# Demux.net
KiCad netlist of a schematic drawn in Altium Designer
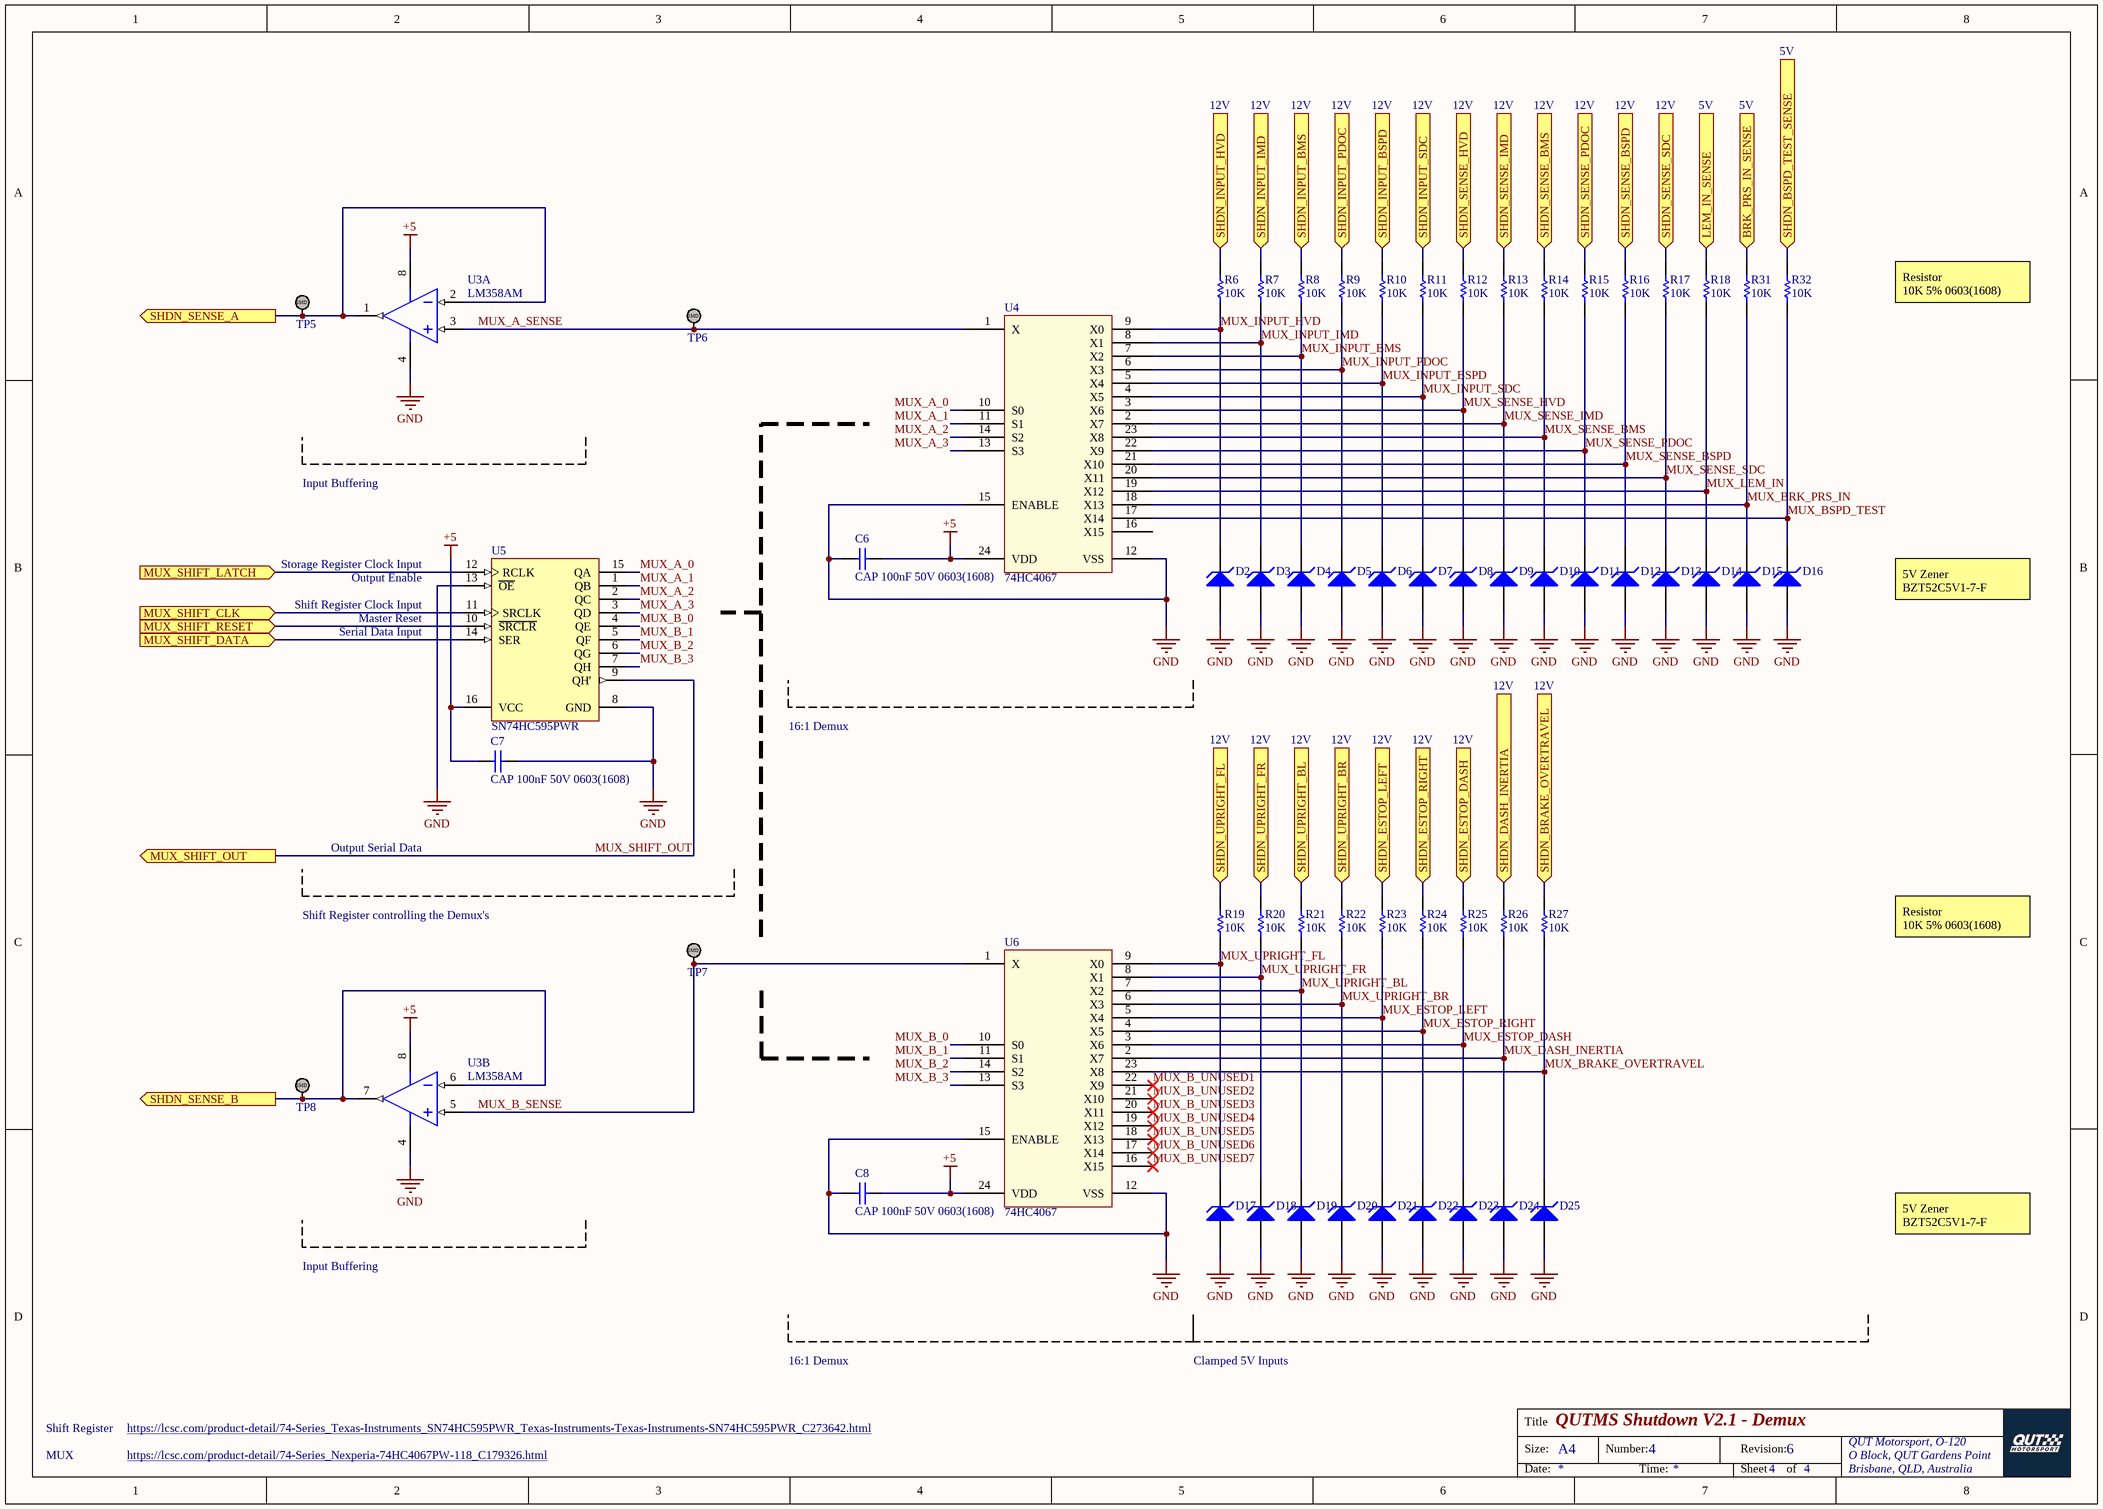
[diagram p0: Demux.SchDoc]

(export (version "E")
  (design (tool "Eeschema 10.0.6"))
  (components
    (comp (ref "C6")
      (value "CAP 100nF 50V 0603(1608)")
      (footprint "CAPC0603(1608)100_L")
      (description "CAP 100nF 50V ±5% 0603 (1608 Metric) Thickness 1mm SMD")
      (fields (field (name "TOLERANCE") "Â±5%"))
      (libsource (lib "Altium Content Vault") (part "CAP"))
    )
    (comp (ref "C7")
      (value "CAP 100nF 50V 0603(1608)")
      (footprint "CAPC0603(1608)100_L")
      (description "CAP 100nF 50V ±5% 0603 (1608 Metric) Thickness 1mm SMD")
      (fields (field (name "TOLERANCE") "Â±5%"))
      (libsource (lib "Altium Content Vault") (part "CAP"))
    )
    (comp (ref "C8")
      (value "CAP 100nF 50V 0603(1608)")
      (footprint "CAPC0603(1608)100_L")
      (description "CAP 100nF 50V ±5% 0603 (1608 Metric) Thickness 1mm SMD")
      (fields (field (name "TOLERANCE") "Â±5%"))
      (libsource (lib "Altium Content Vault") (part "CAP"))
    )
    (comp (ref "D2")
      (value "BZT52C5V1-7-F")
      (footprint "DIOD-SOD123_V")
      (description "Surface Mount Zener Diode, 5.1 V, -65 to 150 degC, 2-Pin SMD (SOD-123), RoHS, Tape and Reel")
      (fields (field (name "MANUFACTURER") "DiodesIncorporated"))
      (libsource (lib "Altium Content Vault") (part "DZEN-AK-2"))
    )
    (comp (ref "D3")
      (value "BZT52C5V1-7-F")
      (footprint "DIOD-SOD123_V")
      (description "Surface Mount Zener Diode, 5.1 V, -65 to 150 degC, 2-Pin SMD (SOD-123), RoHS, Tape and Reel")
      (fields (field (name "MANUFACTURER") "DiodesIncorporated"))
      (libsource (lib "Altium Content Vault") (part "DZEN-AK-2"))
    )
    (comp (ref "D4")
      (value "BZT52C5V1-7-F")
      (footprint "DIOD-SOD123_V")
      (description "Surface Mount Zener Diode, 5.1 V, -65 to 150 degC, 2-Pin SMD (SOD-123), RoHS, Tape and Reel")
      (fields (field (name "MANUFACTURER") "DiodesIncorporated"))
      (libsource (lib "Altium Content Vault") (part "DZEN-AK-2"))
    )
    (comp (ref "D5")
      (value "BZT52C5V1-7-F")
      (footprint "DIOD-SOD123_V")
      (description "Surface Mount Zener Diode, 5.1 V, -65 to 150 degC, 2-Pin SMD (SOD-123), RoHS, Tape and Reel")
      (fields (field (name "MANUFACTURER") "DiodesIncorporated"))
      (libsource (lib "Altium Content Vault") (part "DZEN-AK-2"))
    )
    (comp (ref "D6")
      (value "BZT52C5V1-7-F")
      (footprint "DIOD-SOD123_V")
      (description "Surface Mount Zener Diode, 5.1 V, -65 to 150 degC, 2-Pin SMD (SOD-123), RoHS, Tape and Reel")
      (fields (field (name "MANUFACTURER") "DiodesIncorporated"))
      (libsource (lib "Altium Content Vault") (part "DZEN-AK-2"))
    )
    (comp (ref "D7")
      (value "BZT52C5V1-7-F")
      (footprint "DIOD-SOD123_V")
      (description "Surface Mount Zener Diode, 5.1 V, -65 to 150 degC, 2-Pin SMD (SOD-123), RoHS, Tape and Reel")
      (fields (field (name "MANUFACTURER") "DiodesIncorporated"))
      (libsource (lib "Altium Content Vault") (part "DZEN-AK-2"))
    )
    (comp (ref "D8")
      (value "BZT52C5V1-7-F")
      (footprint "DIOD-SOD123_V")
      (description "Surface Mount Zener Diode, 5.1 V, -65 to 150 degC, 2-Pin SMD (SOD-123), RoHS, Tape and Reel")
      (fields (field (name "MANUFACTURER") "DiodesIncorporated"))
      (libsource (lib "Altium Content Vault") (part "DZEN-AK-2"))
    )
    (comp (ref "D9")
      (value "BZT52C5V1-7-F")
      (footprint "DIOD-SOD123_V")
      (description "Surface Mount Zener Diode, 5.1 V, -65 to 150 degC, 2-Pin SMD (SOD-123), RoHS, Tape and Reel")
      (fields (field (name "MANUFACTURER") "DiodesIncorporated"))
      (libsource (lib "Altium Content Vault") (part "DZEN-AK-2"))
    )
    (comp (ref "D10")
      (value "BZT52C5V1-7-F")
      (footprint "DIOD-SOD123_V")
      (description "Surface Mount Zener Diode, 5.1 V, -65 to 150 degC, 2-Pin SMD (SOD-123), RoHS, Tape and Reel")
      (fields (field (name "MANUFACTURER") "DiodesIncorporated"))
      (libsource (lib "Altium Content Vault") (part "DZEN-AK-2"))
    )
    (comp (ref "D11")
      (value "BZT52C5V1-7-F")
      (footprint "DIOD-SOD123_V")
      (description "Surface Mount Zener Diode, 5.1 V, -65 to 150 degC, 2-Pin SMD (SOD-123), RoHS, Tape and Reel")
      (fields (field (name "MANUFACTURER") "DiodesIncorporated"))
      (libsource (lib "Altium Content Vault") (part "DZEN-AK-2"))
    )
    (comp (ref "D12")
      (value "BZT52C5V1-7-F")
      (footprint "DIOD-SOD123_V")
      (description "Surface Mount Zener Diode, 5.1 V, -65 to 150 degC, 2-Pin SMD (SOD-123), RoHS, Tape and Reel")
      (fields (field (name "MANUFACTURER") "DiodesIncorporated"))
      (libsource (lib "Altium Content Vault") (part "DZEN-AK-2"))
    )
    (comp (ref "D13")
      (value "BZT52C5V1-7-F")
      (footprint "DIOD-SOD123_V")
      (description "Surface Mount Zener Diode, 5.1 V, -65 to 150 degC, 2-Pin SMD (SOD-123), RoHS, Tape and Reel")
      (fields (field (name "MANUFACTURER") "DiodesIncorporated"))
      (libsource (lib "Altium Content Vault") (part "DZEN-AK-2"))
    )
    (comp (ref "D14")
      (value "BZT52C5V1-7-F")
      (footprint "DIOD-SOD123_V")
      (description "Surface Mount Zener Diode, 5.1 V, -65 to 150 degC, 2-Pin SMD (SOD-123), RoHS, Tape and Reel")
      (fields (field (name "MANUFACTURER") "DiodesIncorporated"))
      (libsource (lib "Altium Content Vault") (part "DZEN-AK-2"))
    )
    (comp (ref "D15")
      (value "BZT52C5V1-7-F")
      (footprint "DIOD-SOD123_V")
      (description "Surface Mount Zener Diode, 5.1 V, -65 to 150 degC, 2-Pin SMD (SOD-123), RoHS, Tape and Reel")
      (fields (field (name "MANUFACTURER") "DiodesIncorporated"))
      (libsource (lib "Altium Content Vault") (part "DZEN-AK-2"))
    )
    (comp (ref "D16")
      (value "BZT52C5V1-7-F")
      (footprint "DIOD-SOD123_V")
      (description "Surface Mount Zener Diode, 5.1 V, -65 to 150 degC, 2-Pin SMD (SOD-123), RoHS, Tape and Reel")
      (fields (field (name "MANUFACTURER") "DiodesIncorporated"))
      (libsource (lib "Altium Content Vault") (part "DZEN-AK-2"))
    )
    (comp (ref "D17")
      (value "BZT52C5V1-7-F")
      (footprint "DIOD-SOD123_V")
      (description "Surface Mount Zener Diode, 5.1 V, -65 to 150 degC, 2-Pin SMD (SOD-123), RoHS, Tape and Reel")
      (fields (field (name "MANUFACTURER") "DiodesIncorporated"))
      (libsource (lib "Altium Content Vault") (part "DZEN-AK-2"))
    )
    (comp (ref "D18")
      (value "BZT52C5V1-7-F")
      (footprint "DIOD-SOD123_V")
      (description "Surface Mount Zener Diode, 5.1 V, -65 to 150 degC, 2-Pin SMD (SOD-123), RoHS, Tape and Reel")
      (fields (field (name "MANUFACTURER") "DiodesIncorporated"))
      (libsource (lib "Altium Content Vault") (part "DZEN-AK-2"))
    )
    (comp (ref "D19")
      (value "BZT52C5V1-7-F")
      (footprint "DIOD-SOD123_V")
      (description "Surface Mount Zener Diode, 5.1 V, -65 to 150 degC, 2-Pin SMD (SOD-123), RoHS, Tape and Reel")
      (fields (field (name "MANUFACTURER") "DiodesIncorporated"))
      (libsource (lib "Altium Content Vault") (part "DZEN-AK-2"))
    )
    (comp (ref "D20")
      (value "BZT52C5V1-7-F")
      (footprint "DIOD-SOD123_V")
      (description "Surface Mount Zener Diode, 5.1 V, -65 to 150 degC, 2-Pin SMD (SOD-123), RoHS, Tape and Reel")
      (fields (field (name "MANUFACTURER") "DiodesIncorporated"))
      (libsource (lib "Altium Content Vault") (part "DZEN-AK-2"))
    )
    (comp (ref "D21")
      (value "BZT52C5V1-7-F")
      (footprint "DIOD-SOD123_V")
      (description "Surface Mount Zener Diode, 5.1 V, -65 to 150 degC, 2-Pin SMD (SOD-123), RoHS, Tape and Reel")
      (fields (field (name "MANUFACTURER") "DiodesIncorporated"))
      (libsource (lib "Altium Content Vault") (part "DZEN-AK-2"))
    )
    (comp (ref "D22")
      (value "BZT52C5V1-7-F")
      (footprint "DIOD-SOD123_V")
      (description "Surface Mount Zener Diode, 5.1 V, -65 to 150 degC, 2-Pin SMD (SOD-123), RoHS, Tape and Reel")
      (fields (field (name "MANUFACTURER") "DiodesIncorporated"))
      (libsource (lib "Altium Content Vault") (part "DZEN-AK-2"))
    )
    (comp (ref "D23")
      (value "BZT52C5V1-7-F")
      (footprint "DIOD-SOD123_V")
      (description "Surface Mount Zener Diode, 5.1 V, -65 to 150 degC, 2-Pin SMD (SOD-123), RoHS, Tape and Reel")
      (fields (field (name "MANUFACTURER") "DiodesIncorporated"))
      (libsource (lib "Altium Content Vault") (part "DZEN-AK-2"))
    )
    (comp (ref "D24")
      (value "BZT52C5V1-7-F")
      (footprint "DIOD-SOD123_V")
      (description "Surface Mount Zener Diode, 5.1 V, -65 to 150 degC, 2-Pin SMD (SOD-123), RoHS, Tape and Reel")
      (fields (field (name "MANUFACTURER") "DiodesIncorporated"))
      (libsource (lib "Altium Content Vault") (part "DZEN-AK-2"))
    )
    (comp (ref "D25")
      (value "BZT52C5V1-7-F")
      (footprint "DIOD-SOD123_V")
      (description "Surface Mount Zener Diode, 5.1 V, -65 to 150 degC, 2-Pin SMD (SOD-123), RoHS, Tape and Reel")
      (fields (field (name "MANUFACTURER") "DiodesIncorporated"))
      (libsource (lib "Altium Content Vault") (part "DZEN-AK-2"))
    )
    (comp (ref "R6")
      (value "10K")
      (footprint "RESC0603(1608)_N")
      (description "10K 0.1W 5% 0603 (1608 Metric)  SMD")
      (fields (field (name "TOLERANCE") "5 %") (field (name "POWER") "0.1 W"))
      (libsource (lib "Altium Content Vault") (part "RES"))
    )
    (comp (ref "R7")
      (value "10K")
      (footprint "RESC0603(1608)_N")
      (description "10K 0.1W 5% 0603 (1608 Metric)  SMD")
      (fields (field (name "TOLERANCE") "5 %") (field (name "POWER") "0.1 W"))
      (libsource (lib "Altium Content Vault") (part "RES"))
    )
    (comp (ref "R8")
      (value "10K")
      (footprint "RESC0603(1608)_N")
      (description "10K 0.1W 5% 0603 (1608 Metric)  SMD")
      (fields (field (name "TOLERANCE") "5 %") (field (name "POWER") "0.1 W"))
      (libsource (lib "Altium Content Vault") (part "RES"))
    )
    (comp (ref "R9")
      (value "10K")
      (footprint "RESC0603(1608)_N")
      (description "10K 0.1W 5% 0603 (1608 Metric)  SMD")
      (fields (field (name "TOLERANCE") "5 %") (field (name "POWER") "0.1 W"))
      (libsource (lib "Altium Content Vault") (part "RES"))
    )
    (comp (ref "R10")
      (value "10K")
      (footprint "RESC0603(1608)_N")
      (description "10K 0.1W 5% 0603 (1608 Metric)  SMD")
      (fields (field (name "TOLERANCE") "5 %") (field (name "POWER") "0.1 W"))
      (libsource (lib "Altium Content Vault") (part "RES"))
    )
    (comp (ref "R11")
      (value "10K")
      (footprint "RESC0603(1608)_N")
      (description "10K 0.1W 5% 0603 (1608 Metric)  SMD")
      (fields (field (name "TOLERANCE") "5 %") (field (name "POWER") "0.1 W"))
      (libsource (lib "Altium Content Vault") (part "RES"))
    )
    (comp (ref "R12")
      (value "10K")
      (footprint "RESC0603(1608)_N")
      (description "10K 0.1W 5% 0603 (1608 Metric)  SMD")
      (fields (field (name "TOLERANCE") "5 %") (field (name "POWER") "0.1 W"))
      (libsource (lib "Altium Content Vault") (part "RES"))
    )
    (comp (ref "R13")
      (value "10K")
      (footprint "RESC0603(1608)_N")
      (description "10K 0.1W 5% 0603 (1608 Metric)  SMD")
      (fields (field (name "TOLERANCE") "5 %") (field (name "POWER") "0.1 W"))
      (libsource (lib "Altium Content Vault") (part "RES"))
    )
    (comp (ref "R14")
      (value "10K")
      (footprint "RESC0603(1608)_N")
      (description "10K 0.1W 5% 0603 (1608 Metric)  SMD")
      (fields (field (name "TOLERANCE") "5 %") (field (name "POWER") "0.1 W"))
      (libsource (lib "Altium Content Vault") (part "RES"))
    )
    (comp (ref "R15")
      (value "10K")
      (footprint "RESC0603(1608)_N")
      (description "10K 0.1W 5% 0603 (1608 Metric)  SMD")
      (fields (field (name "TOLERANCE") "5 %") (field (name "POWER") "0.1 W"))
      (libsource (lib "Altium Content Vault") (part "RES"))
    )
    (comp (ref "R16")
      (value "10K")
      (footprint "RESC0603(1608)_N")
      (description "10K 0.1W 5% 0603 (1608 Metric)  SMD")
      (fields (field (name "TOLERANCE") "5 %") (field (name "POWER") "0.1 W"))
      (libsource (lib "Altium Content Vault") (part "RES"))
    )
    (comp (ref "R17")
      (value "10K")
      (footprint "RESC0603(1608)_N")
      (description "10K 0.1W 5% 0603 (1608 Metric)  SMD")
      (fields (field (name "TOLERANCE") "5 %") (field (name "POWER") "0.1 W"))
      (libsource (lib "Altium Content Vault") (part "RES"))
    )
    (comp (ref "R18")
      (value "10K")
      (footprint "RESC0603(1608)_N")
      (description "10K 0.1W 5% 0603 (1608 Metric)  SMD")
      (fields (field (name "TOLERANCE") "5 %") (field (name "POWER") "0.1 W"))
      (libsource (lib "Altium Content Vault") (part "RES"))
    )
    (comp (ref "R19")
      (value "10K")
      (footprint "RESC0603(1608)_N")
      (description "10K 0.1W 5% 0603 (1608 Metric)  SMD")
      (fields (field (name "TOLERANCE") "5 %") (field (name "POWER") "0.1 W"))
      (libsource (lib "Altium Content Vault") (part "RES"))
    )
    (comp (ref "R20")
      (value "10K")
      (footprint "RESC0603(1608)_N")
      (description "10K 0.1W 5% 0603 (1608 Metric)  SMD")
      (fields (field (name "TOLERANCE") "5 %") (field (name "POWER") "0.1 W"))
      (libsource (lib "Altium Content Vault") (part "RES"))
    )
    (comp (ref "R21")
      (value "10K")
      (footprint "RESC0603(1608)_N")
      (description "10K 0.1W 5% 0603 (1608 Metric)  SMD")
      (fields (field (name "TOLERANCE") "5 %") (field (name "POWER") "0.1 W"))
      (libsource (lib "Altium Content Vault") (part "RES"))
    )
    (comp (ref "R22")
      (value "10K")
      (footprint "RESC0603(1608)_N")
      (description "10K 0.1W 5% 0603 (1608 Metric)  SMD")
      (fields (field (name "TOLERANCE") "5 %") (field (name "POWER") "0.1 W"))
      (libsource (lib "Altium Content Vault") (part "RES"))
    )
    (comp (ref "R23")
      (value "10K")
      (footprint "RESC0603(1608)_N")
      (description "10K 0.1W 5% 0603 (1608 Metric)  SMD")
      (fields (field (name "TOLERANCE") "5 %") (field (name "POWER") "0.1 W"))
      (libsource (lib "Altium Content Vault") (part "RES"))
    )
    (comp (ref "R24")
      (value "10K")
      (footprint "RESC0603(1608)_N")
      (description "10K 0.1W 5% 0603 (1608 Metric)  SMD")
      (fields (field (name "TOLERANCE") "5 %") (field (name "POWER") "0.1 W"))
      (libsource (lib "Altium Content Vault") (part "RES"))
    )
    (comp (ref "R25")
      (value "10K")
      (footprint "RESC0603(1608)_N")
      (description "10K 0.1W 5% 0603 (1608 Metric)  SMD")
      (fields (field (name "TOLERANCE") "5 %") (field (name "POWER") "0.1 W"))
      (libsource (lib "Altium Content Vault") (part "RES"))
    )
    (comp (ref "R26")
      (value "10K")
      (footprint "RESC0603(1608)_N")
      (description "10K 0.1W 5% 0603 (1608 Metric)  SMD")
      (fields (field (name "TOLERANCE") "5 %") (field (name "POWER") "0.1 W"))
      (libsource (lib "Altium Content Vault") (part "RES"))
    )
    (comp (ref "R27")
      (value "10K")
      (footprint "RESC0603(1608)_N")
      (description "10K 0.1W 5% 0603 (1608 Metric)  SMD")
      (fields (field (name "TOLERANCE") "5 %") (field (name "POWER") "0.1 W"))
      (libsource (lib "Altium Content Vault") (part "RES"))
    )
    (comp (ref "R31")
      (value "10K")
      (footprint "RESC0603(1608)_N")
      (description "10K 0.1W 5% 0603 (1608 Metric)  SMD")
      (fields (field (name "TOLERANCE") "5 %") (field (name "POWER") "0.1 W"))
      (libsource (lib "Altium Content Vault") (part "RES"))
    )
    (comp (ref "R32")
      (value "10K")
      (footprint "RESC0603(1608)_N")
      (description "10K 0.1W 5% 0603 (1608 Metric)  SMD")
      (fields (field (name "TOLERANCE") "5 %") (field (name "POWER") "0.1 W"))
      (libsource (lib "Altium Content Vault") (part "RES"))
    )
    (comp (ref "TP5")
      (value "TestPoint_SMD")
      (footprint "TestPointSMD")
      (libsource (lib "StandardTest") (part "TestPoint_SMD"))
    )
    (comp (ref "TP6")
      (value "TestPoint_SMD")
      (footprint "TestPointSMD")
      (libsource (lib "StandardTest") (part "TestPoint_SMD"))
    )
    (comp (ref "TP7")
      (value "TestPoint_SMD")
      (footprint "TestPointSMD")
      (libsource (lib "StandardTest") (part "TestPoint_SMD"))
    )
    (comp (ref "TP8")
      (value "TestPoint_SMD")
      (footprint "TestPointSMD")
      (libsource (lib "StandardTest") (part "TestPoint_SMD"))
    )
    (comp (ref "U3")
      (value "LM358AM")
      (footprint "D0008A_M")
      (description "Low Power Dual Operational Amplifier, 8-pin Narrow SOIC")
      (fields (field (name "MANUFACTURER") "Texas Instruments"))
      (libsource (lib "Altium Content Vault") (part "AMP-OPA-LM158-8"))
    )
    (comp (ref "U4")
      (value "74HC4067")
      (footprint "74HC4067 TSSOP24")
      (libsource (lib "QUTMS_MUXLibrary") (part "74HC4067"))
    )
    (comp (ref "U5")
      (value "SN74HC595PWR")
      (footprint "PW0016A_L")
      (description "8-Bit Shift Registers With 3-State Output Registers, PW0016A, LARGE T&R")
      (fields
        (field (name "GENERIC PART NUMBER") "SN74HC595")
        (field (name "MANUFACTURER") "Texas Instruments")
      )
      (libsource (lib "Altium Content Vault") (part "TI-SN74XHCT595X_SN74LV595A-16"))
    )
    (comp (ref "U6")
      (value "74HC4067")
      (footprint "74HC4067 TSSOP24")
      (libsource (lib "QUTMS_MUXLibrary") (part "74HC4067"))
    )
  )
  (nets
    (net (code "1") (name "+5") (class "Default")
      (node (ref "C6") (pin "1") (pinfunction "1_1") (pintype "passive"))
      (node (ref "C7") (pin "2") (pinfunction "2_2") (pintype "passive"))
      (node (ref "C8") (pin "1") (pinfunction "1_1") (pintype "passive"))
      (node (ref "U3") (pin "8") (pinfunction "V+_8") (pintype "power_in"))
      (node (ref "U4") (pin "24") (pinfunction "VDD_24") (pintype "passive"))
      (node (ref "U5") (pin "16") (pinfunction "VCC_16") (pintype "power_in"))
      (node (ref "U6") (pin "24") (pinfunction "VDD_24") (pintype "passive"))
    )
    (net (code "2") (name "/BRK_PRS_IN_SENSE") (class "Default")
      (node (ref "R31") (pin "1") (pinfunction "1_1") (pintype "passive"))
    )
    (net (code "3") (name "/LEM_IN_SENSE") (class "Default")
      (node (ref "R18") (pin "1") (pinfunction "1_1") (pintype "passive"))
    )
    (net (code "4") (name "/MUX_A_0") (class "Default")
      (node (ref "U4") (pin "10") (pinfunction "S0_10") (pintype "passive"))
      (node (ref "U5") (pin "15") (pinfunction "QA_15") (pintype "tri_state"))
    )
    (net (code "5") (name "/MUX_A_1") (class "Default")
      (node (ref "U4") (pin "11") (pinfunction "S1_11") (pintype "passive"))
      (node (ref "U5") (pin "1") (pinfunction "QB_1") (pintype "tri_state"))
    )
    (net (code "6") (name "/MUX_A_2") (class "Default")
      (node (ref "U4") (pin "14") (pinfunction "S2_14") (pintype "passive"))
      (node (ref "U5") (pin "2") (pinfunction "QC_2") (pintype "tri_state"))
    )
    (net (code "7") (name "/MUX_A_3") (class "Default")
      (node (ref "U4") (pin "13") (pinfunction "S3_13") (pintype "passive"))
      (node (ref "U5") (pin "3") (pinfunction "QD_3") (pintype "tri_state"))
    )
    (net (code "8") (name "/MUX_A_SENSE") (class "Default")
      (node (ref "TP6") (pin "1") (pinfunction "1_1") (pintype "passive"))
      (node (ref "U3") (pin "3") (pinfunction "INA+_3") (pintype "input"))
      (node (ref "U4") (pin "1") (pinfunction "X_1") (pintype "passive"))
    )
    (net (code "9") (name "/MUX_BRAKE_OVERTRAVEL") (class "Default")
      (node (ref "D25") (pin "2") (pinfunction "K_2") (pintype "passive"))
      (node (ref "R27") (pin "2") (pinfunction "2_2") (pintype "passive"))
      (node (ref "U6") (pin "23") (pinfunction "X8_23") (pintype "passive"))
    )
    (net (code "10") (name "/MUX_BRK_PRS_IN") (class "Default")
      (node (ref "D15") (pin "2") (pinfunction "K_2") (pintype "passive"))
      (node (ref "R31") (pin "2") (pinfunction "2_2") (pintype "passive"))
      (node (ref "U4") (pin "18") (pinfunction "X13_18") (pintype "passive"))
    )
    (net (code "11") (name "/MUX_BSPD_TEST") (class "Default")
      (node (ref "D16") (pin "2") (pinfunction "K_2") (pintype "passive"))
      (node (ref "R32") (pin "2") (pinfunction "2_2") (pintype "passive"))
      (node (ref "U4") (pin "17") (pinfunction "X14_17") (pintype "passive"))
    )
    (net (code "12") (name "/MUX_B_0") (class "Default")
      (node (ref "U5") (pin "4") (pinfunction "QE_4") (pintype "tri_state"))
      (node (ref "U6") (pin "10") (pinfunction "S0_10") (pintype "passive"))
    )
    (net (code "13") (name "/MUX_B_1") (class "Default")
      (node (ref "U5") (pin "5") (pinfunction "QF_5") (pintype "tri_state"))
      (node (ref "U6") (pin "11") (pinfunction "S1_11") (pintype "passive"))
    )
    (net (code "14") (name "/MUX_B_2") (class "Default")
      (node (ref "U5") (pin "6") (pinfunction "QG_6") (pintype "tri_state"))
      (node (ref "U6") (pin "14") (pinfunction "S2_14") (pintype "passive"))
    )
    (net (code "15") (name "/MUX_B_3") (class "Default")
      (node (ref "U5") (pin "7") (pinfunction "QH_7") (pintype "tri_state"))
      (node (ref "U6") (pin "13") (pinfunction "S3_13") (pintype "passive"))
    )
    (net (code "16") (name "/MUX_B_SENSE") (class "Default")
      (node (ref "TP7") (pin "1") (pinfunction "1_1") (pintype "passive"))
      (node (ref "U3") (pin "5") (pinfunction "INB+_5") (pintype "input"))
      (node (ref "U6") (pin "1") (pinfunction "X_1") (pintype "passive"))
    )
    (net (code "17") (name "/MUX_B_UNUSED1") (class "Default")
      (node (ref "U6") (pin "22") (pinfunction "X9_22") (pintype "passive+no_connect"))
    )
    (net (code "18") (name "/MUX_B_UNUSED2") (class "Default")
      (node (ref "U6") (pin "21") (pinfunction "X10_21") (pintype "passive+no_connect"))
    )
    (net (code "19") (name "/MUX_B_UNUSED3") (class "Default")
      (node (ref "U6") (pin "20") (pinfunction "X11_20") (pintype "passive+no_connect"))
    )
    (net (code "20") (name "/MUX_B_UNUSED4") (class "Default")
      (node (ref "U6") (pin "19") (pinfunction "X12_19") (pintype "passive+no_connect"))
    )
    (net (code "21") (name "/MUX_B_UNUSED5") (class "Default")
      (node (ref "U6") (pin "18") (pinfunction "X13_18") (pintype "passive+no_connect"))
    )
    (net (code "22") (name "/MUX_B_UNUSED6") (class "Default")
      (node (ref "U6") (pin "17") (pinfunction "X14_17") (pintype "passive+no_connect"))
    )
    (net (code "23") (name "/MUX_B_UNUSED7") (class "Default")
      (node (ref "U6") (pin "16") (pinfunction "X15_16") (pintype "passive+no_connect"))
    )
    (net (code "24") (name "/MUX_DASH_INERTIA") (class "Default")
      (node (ref "D24") (pin "2") (pinfunction "K_2") (pintype "passive"))
      (node (ref "R26") (pin "2") (pinfunction "2_2") (pintype "passive"))
      (node (ref "U6") (pin "2") (pinfunction "X7_2") (pintype "passive"))
    )
    (net (code "25") (name "/MUX_ESTOP_DASH") (class "Default")
      (node (ref "D23") (pin "2") (pinfunction "K_2") (pintype "passive"))
      (node (ref "R25") (pin "2") (pinfunction "2_2") (pintype "passive"))
      (node (ref "U6") (pin "3") (pinfunction "X6_3") (pintype "passive"))
    )
    (net (code "26") (name "/MUX_ESTOP_LEFT") (class "Default")
      (node (ref "D21") (pin "2") (pinfunction "K_2") (pintype "passive"))
      (node (ref "R23") (pin "2") (pinfunction "2_2") (pintype "passive"))
      (node (ref "U6") (pin "5") (pinfunction "X4_5") (pintype "passive"))
    )
    (net (code "27") (name "/MUX_ESTOP_RIGHT") (class "Default")
      (node (ref "D22") (pin "2") (pinfunction "K_2") (pintype "passive"))
      (node (ref "R24") (pin "2") (pinfunction "2_2") (pintype "passive"))
      (node (ref "U6") (pin "4") (pinfunction "X5_4") (pintype "passive"))
    )
    (net (code "28") (name "/MUX_INPUT_BMS") (class "Default")
      (node (ref "D4") (pin "2") (pinfunction "K_2") (pintype "passive"))
      (node (ref "R8") (pin "2") (pinfunction "2_2") (pintype "passive"))
      (node (ref "U4") (pin "7") (pinfunction "X2_7") (pintype "passive"))
    )
    (net (code "29") (name "/MUX_INPUT_BSPD") (class "Default")
      (node (ref "D6") (pin "2") (pinfunction "K_2") (pintype "passive"))
      (node (ref "R10") (pin "2") (pinfunction "2_2") (pintype "passive"))
      (node (ref "U4") (pin "5") (pinfunction "X4_5") (pintype "passive"))
    )
    (net (code "30") (name "/MUX_INPUT_HVD") (class "Default")
      (node (ref "D2") (pin "2") (pinfunction "K_2") (pintype "passive"))
      (node (ref "R6") (pin "2") (pinfunction "2_2") (pintype "passive"))
      (node (ref "U4") (pin "9") (pinfunction "X0_9") (pintype "passive"))
    )
    (net (code "31") (name "/MUX_INPUT_IMD") (class "Default")
      (node (ref "D3") (pin "2") (pinfunction "K_2") (pintype "passive"))
      (node (ref "R7") (pin "2") (pinfunction "2_2") (pintype "passive"))
      (node (ref "U4") (pin "8") (pinfunction "X1_8") (pintype "passive"))
    )
    (net (code "32") (name "/MUX_INPUT_PDOC") (class "Default")
      (node (ref "D5") (pin "2") (pinfunction "K_2") (pintype "passive"))
      (node (ref "R9") (pin "2") (pinfunction "2_2") (pintype "passive"))
      (node (ref "U4") (pin "6") (pinfunction "X3_6") (pintype "passive"))
    )
    (net (code "33") (name "/MUX_INPUT_SDC") (class "Default")
      (node (ref "D7") (pin "2") (pinfunction "K_2") (pintype "passive"))
      (node (ref "R11") (pin "2") (pinfunction "2_2") (pintype "passive"))
      (node (ref "U4") (pin "4") (pinfunction "X5_4") (pintype "passive"))
    )
    (net (code "34") (name "/MUX_LEM_IN") (class "Default")
      (node (ref "D14") (pin "2") (pinfunction "K_2") (pintype "passive"))
      (node (ref "R18") (pin "2") (pinfunction "2_2") (pintype "passive"))
      (node (ref "U4") (pin "19") (pinfunction "X12_19") (pintype "passive"))
    )
    (net (code "35") (name "/MUX_SENSE_BMS") (class "Default")
      (node (ref "D10") (pin "2") (pinfunction "K_2") (pintype "passive"))
      (node (ref "R14") (pin "2") (pinfunction "2_2") (pintype "passive"))
      (node (ref "U4") (pin "23") (pinfunction "X8_23") (pintype "passive"))
    )
    (net (code "36") (name "/MUX_SENSE_BSPD") (class "Default")
      (node (ref "D12") (pin "2") (pinfunction "K_2") (pintype "passive"))
      (node (ref "R16") (pin "2") (pinfunction "2_2") (pintype "passive"))
      (node (ref "U4") (pin "21") (pinfunction "X10_21") (pintype "passive"))
    )
    (net (code "37") (name "/MUX_SENSE_HVD") (class "Default")
      (node (ref "D8") (pin "2") (pinfunction "K_2") (pintype "passive"))
      (node (ref "R12") (pin "2") (pinfunction "2_2") (pintype "passive"))
      (node (ref "U4") (pin "3") (pinfunction "X6_3") (pintype "passive"))
    )
    (net (code "38") (name "/MUX_SENSE_IMD") (class "Default")
      (node (ref "D9") (pin "2") (pinfunction "K_2") (pintype "passive"))
      (node (ref "R13") (pin "2") (pinfunction "2_2") (pintype "passive"))
      (node (ref "U4") (pin "2") (pinfunction "X7_2") (pintype "passive"))
    )
    (net (code "39") (name "/MUX_SENSE_PDOC") (class "Default")
      (node (ref "D11") (pin "2") (pinfunction "K_2") (pintype "passive"))
      (node (ref "R15") (pin "2") (pinfunction "2_2") (pintype "passive"))
      (node (ref "U4") (pin "22") (pinfunction "X9_22") (pintype "passive"))
    )
    (net (code "40") (name "/MUX_SENSE_SDC") (class "Default")
      (node (ref "D13") (pin "2") (pinfunction "K_2") (pintype "passive"))
      (node (ref "R17") (pin "2") (pinfunction "2_2") (pintype "passive"))
      (node (ref "U4") (pin "20") (pinfunction "X11_20") (pintype "passive"))
    )
    (net (code "41") (name "/MUX_SHIFT_CLK") (class "Default")
      (node (ref "U5") (pin "11") (pinfunction "SRCLK_11") (pintype "input"))
    )
    (net (code "42") (name "/MUX_SHIFT_DATA") (class "Default")
      (node (ref "U5") (pin "14") (pinfunction "SER_14") (pintype "input"))
    )
    (net (code "43") (name "/MUX_SHIFT_LATCH") (class "Default")
      (node (ref "U5") (pin "12") (pinfunction "RCLK_12") (pintype "input"))
    )
    (net (code "44") (name "/MUX_SHIFT_OUT") (class "Default")
      (node (ref "U5") (pin "9") (pinfunction "QH'_9") (pintype "output"))
    )
    (net (code "45") (name "/MUX_SHIFT_RESET") (class "Default")
      (node (ref "U5") (pin "10") (pinfunction "~{SRCLR}_10") (pintype "input"))
    )
    (net (code "46") (name "/MUX_UPRIGHT_BL") (class "Default")
      (node (ref "D19") (pin "2") (pinfunction "K_2") (pintype "passive"))
      (node (ref "R21") (pin "2") (pinfunction "2_2") (pintype "passive"))
      (node (ref "U6") (pin "7") (pinfunction "X2_7") (pintype "passive"))
    )
    (net (code "47") (name "/MUX_UPRIGHT_BR") (class "Default")
      (node (ref "D20") (pin "2") (pinfunction "K_2") (pintype "passive"))
      (node (ref "R22") (pin "2") (pinfunction "2_2") (pintype "passive"))
      (node (ref "U6") (pin "6") (pinfunction "X3_6") (pintype "passive"))
    )
    (net (code "48") (name "/MUX_UPRIGHT_FL") (class "Default")
      (node (ref "D17") (pin "2") (pinfunction "K_2") (pintype "passive"))
      (node (ref "R19") (pin "2") (pinfunction "2_2") (pintype "passive"))
      (node (ref "U6") (pin "9") (pinfunction "X0_9") (pintype "passive"))
    )
    (net (code "49") (name "/MUX_UPRIGHT_FR") (class "Default")
      (node (ref "D18") (pin "2") (pinfunction "K_2") (pintype "passive"))
      (node (ref "R20") (pin "2") (pinfunction "2_2") (pintype "passive"))
      (node (ref "U6") (pin "8") (pinfunction "X1_8") (pintype "passive"))
    )
    (net (code "50") (name "/SHDN_BRAKE_OVERTRAVEL") (class "Default")
      (node (ref "R27") (pin "1") (pinfunction "1_1") (pintype "passive"))
    )
    (net (code "51") (name "/SHDN_BSPD_TEST_SENSE") (class "Default")
      (node (ref "R32") (pin "1") (pinfunction "1_1") (pintype "passive"))
    )
    (net (code "52") (name "/SHDN_DASH_INERTIA") (class "Default")
      (node (ref "R26") (pin "1") (pinfunction "1_1") (pintype "passive"))
    )
    (net (code "53") (name "/SHDN_ESTOP_DASH") (class "Default")
      (node (ref "R25") (pin "1") (pinfunction "1_1") (pintype "passive"))
    )
    (net (code "54") (name "/SHDN_ESTOP_LEFT") (class "Default")
      (node (ref "R23") (pin "1") (pinfunction "1_1") (pintype "passive"))
    )
    (net (code "55") (name "/SHDN_ESTOP_RIGHT") (class "Default")
      (node (ref "R24") (pin "1") (pinfunction "1_1") (pintype "passive"))
    )
    (net (code "56") (name "/SHDN_INPUT_BMS") (class "Default")
      (node (ref "R8") (pin "1") (pinfunction "1_1") (pintype "passive"))
    )
    (net (code "57") (name "/SHDN_INPUT_BSPD") (class "Default")
      (node (ref "R10") (pin "1") (pinfunction "1_1") (pintype "passive"))
    )
    (net (code "58") (name "/SHDN_INPUT_HVD") (class "Default")
      (node (ref "R6") (pin "1") (pinfunction "1_1") (pintype "passive"))
    )
    (net (code "59") (name "/SHDN_INPUT_IMD") (class "Default")
      (node (ref "R7") (pin "1") (pinfunction "1_1") (pintype "passive"))
    )
    (net (code "60") (name "/SHDN_INPUT_PDOC") (class "Default")
      (node (ref "R9") (pin "1") (pinfunction "1_1") (pintype "passive"))
    )
    (net (code "61") (name "/SHDN_INPUT_SDC") (class "Default")
      (node (ref "R11") (pin "1") (pinfunction "1_1") (pintype "passive"))
    )
    (net (code "62") (name "/SHDN_SENSE_A") (class "Default")
      (node (ref "TP5") (pin "1") (pinfunction "1_1") (pintype "passive"))
      (node (ref "U3") (pin "1") (pinfunction "OUTA_1") (pintype "output"))
      (node (ref "U3") (pin "2") (pinfunction "INA-_2") (pintype "input"))
    )
    (net (code "63") (name "/SHDN_SENSE_B") (class "Default")
      (node (ref "TP8") (pin "1") (pinfunction "1_1") (pintype "passive"))
      (node (ref "U3") (pin "6") (pinfunction "INB-_6") (pintype "input"))
      (node (ref "U3") (pin "7") (pinfunction "OUTB_7") (pintype "output"))
    )
    (net (code "64") (name "/SHDN_SENSE_BMS") (class "Default")
      (node (ref "R14") (pin "1") (pinfunction "1_1") (pintype "passive"))
    )
    (net (code "65") (name "/SHDN_SENSE_BSPD") (class "Default")
      (node (ref "R16") (pin "1") (pinfunction "1_1") (pintype "passive"))
    )
    (net (code "66") (name "/SHDN_SENSE_HVD") (class "Default")
      (node (ref "R12") (pin "1") (pinfunction "1_1") (pintype "passive"))
    )
    (net (code "67") (name "/SHDN_SENSE_IMD") (class "Default")
      (node (ref "R13") (pin "1") (pinfunction "1_1") (pintype "passive"))
    )
    (net (code "68") (name "/SHDN_SENSE_PDOC") (class "Default")
      (node (ref "R15") (pin "1") (pinfunction "1_1") (pintype "passive"))
    )
    (net (code "69") (name "/SHDN_SENSE_SDC") (class "Default")
      (node (ref "R17") (pin "1") (pinfunction "1_1") (pintype "passive"))
    )
    (net (code "70") (name "/SHDN_UPRIGHT_BL") (class "Default")
      (node (ref "R21") (pin "1") (pinfunction "1_1") (pintype "passive"))
    )
    (net (code "71") (name "/SHDN_UPRIGHT_BR") (class "Default")
      (node (ref "R22") (pin "1") (pinfunction "1_1") (pintype "passive"))
    )
    (net (code "72") (name "/SHDN_UPRIGHT_FL") (class "Default")
      (node (ref "R19") (pin "1") (pinfunction "1_1") (pintype "passive"))
    )
    (net (code "73") (name "/SHDN_UPRIGHT_FR") (class "Default")
      (node (ref "R20") (pin "1") (pinfunction "1_1") (pintype "passive"))
    )
    (net (code "74") (name "GND") (class "Default")
      (node (ref "C6") (pin "2") (pinfunction "2_2") (pintype "passive"))
      (node (ref "C7") (pin "1") (pinfunction "1_1") (pintype "passive"))
      (node (ref "C8") (pin "2") (pinfunction "2_2") (pintype "passive"))
      (node (ref "D10") (pin "1") (pinfunction "A_1") (pintype "passive"))
      (node (ref "D11") (pin "1") (pinfunction "A_1") (pintype "passive"))
      (node (ref "D12") (pin "1") (pinfunction "A_1") (pintype "passive"))
      (node (ref "D13") (pin "1") (pinfunction "A_1") (pintype "passive"))
      (node (ref "D14") (pin "1") (pinfunction "A_1") (pintype "passive"))
      (node (ref "D15") (pin "1") (pinfunction "A_1") (pintype "passive"))
      (node (ref "D16") (pin "1") (pinfunction "A_1") (pintype "passive"))
      (node (ref "D17") (pin "1") (pinfunction "A_1") (pintype "passive"))
      (node (ref "D18") (pin "1") (pinfunction "A_1") (pintype "passive"))
      (node (ref "D19") (pin "1") (pinfunction "A_1") (pintype "passive"))
      (node (ref "D2") (pin "1") (pinfunction "A_1") (pintype "passive"))
      (node (ref "D20") (pin "1") (pinfunction "A_1") (pintype "passive"))
      (node (ref "D21") (pin "1") (pinfunction "A_1") (pintype "passive"))
      (node (ref "D22") (pin "1") (pinfunction "A_1") (pintype "passive"))
      (node (ref "D23") (pin "1") (pinfunction "A_1") (pintype "passive"))
      (node (ref "D24") (pin "1") (pinfunction "A_1") (pintype "passive"))
      (node (ref "D25") (pin "1") (pinfunction "A_1") (pintype "passive"))
      (node (ref "D3") (pin "1") (pinfunction "A_1") (pintype "passive"))
      (node (ref "D4") (pin "1") (pinfunction "A_1") (pintype "passive"))
      (node (ref "D5") (pin "1") (pinfunction "A_1") (pintype "passive"))
      (node (ref "D6") (pin "1") (pinfunction "A_1") (pintype "passive"))
      (node (ref "D7") (pin "1") (pinfunction "A_1") (pintype "passive"))
      (node (ref "D8") (pin "1") (pinfunction "A_1") (pintype "passive"))
      (node (ref "D9") (pin "1") (pinfunction "A_1") (pintype "passive"))
      (node (ref "U3") (pin "4") (pinfunction "GND_4") (pintype "power_in"))
      (node (ref "U4") (pin "12") (pinfunction "VSS_12") (pintype "passive"))
      (node (ref "U4") (pin "15") (pinfunction "ENABLE_15") (pintype "passive"))
      (node (ref "U5") (pin "13") (pinfunction "~{OE}_13") (pintype "input"))
      (node (ref "U5") (pin "8") (pinfunction "GND_8") (pintype "power_in"))
      (node (ref "U6") (pin "12") (pinfunction "VSS_12") (pintype "passive"))
      (node (ref "U6") (pin "15") (pinfunction "ENABLE_15") (pintype "passive"))
    )
    (net (code "75") (name "unconnected-(U4-X15-Pad16)") (class "Default")
      (node (ref "U4") (pin "16") (pinfunction "X15_16") (pintype "passive"))
    )
  )
)
